# GatewayModbus.net
KiCad netlist of a schematic drawn in Altium Designer
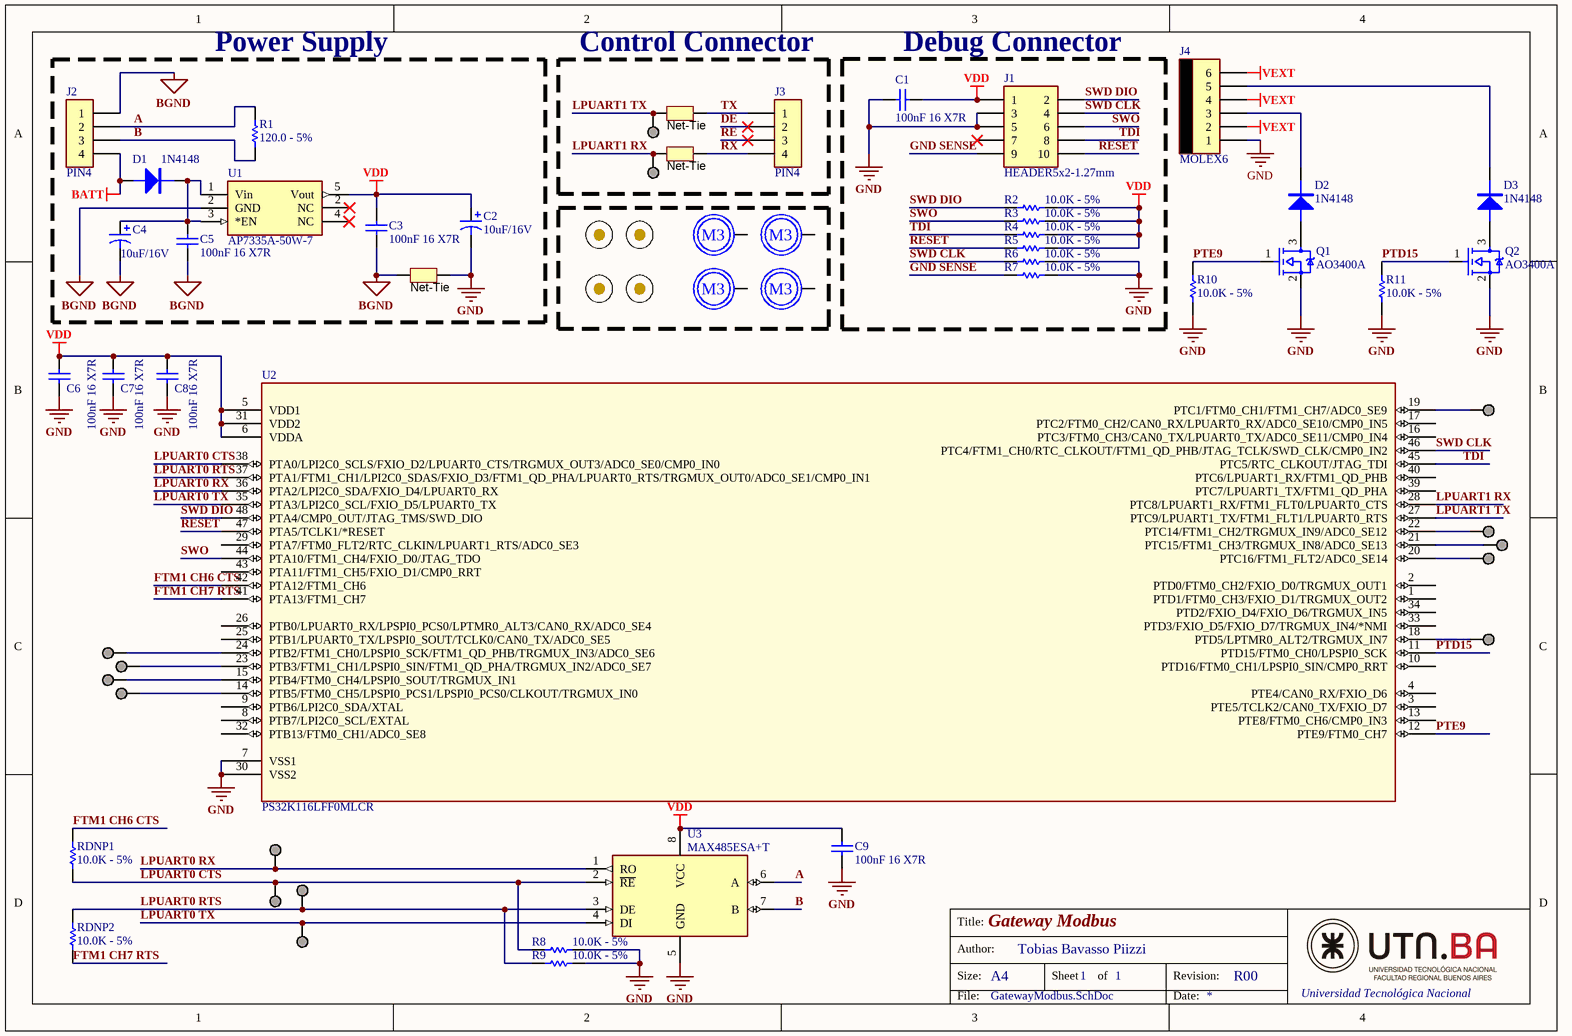
[diagram p0: GatewayModbus.SchDoc]

(export (version "E")
  (design (tool "Eeschema 10.0.6"))
  (components
    (comp (ref "C1")
      (value "100nF 16 X7R")
      (footprint "CAPC0603")
      (description "SMD Ceramic Chip Capacitor 0603")
      (libsource (lib "capacitors") (part "CAPC0603"))
    )
    (comp (ref "C2")
      (value "10uF/16V")
      (footprint "CAP POL TANT 1206")
      (description "Polarized Capacitor Tantalium")
      (libsource (lib "capacitors") (part "CAP POL TANT"))
    )
    (comp (ref "C3")
      (value "100nF 16 X7R")
      (footprint "CAPC0603")
      (description "SMD Ceramic Chip Capacitor 0603")
      (libsource (lib "capacitors") (part "CAPC0603"))
    )
    (comp (ref "C4")
      (value "10uF/16V")
      (footprint "CAP POL TANT 1206")
      (description "Polarized Capacitor Tantalium")
      (libsource (lib "capacitors") (part "CAP POL TANT"))
    )
    (comp (ref "C5")
      (value "100nF 16 X7R")
      (footprint "CAPC0603")
      (description "SMD Ceramic Chip Capacitor 0603")
      (libsource (lib "capacitors") (part "CAPC0603"))
    )
    (comp (ref "C6")
      (value "100nF 16 X7R")
      (footprint "CAPC0603")
      (description "SMD Ceramic Chip Capacitor 0603")
      (libsource (lib "capacitors") (part "CAPC0603"))
    )
    (comp (ref "C7")
      (value "100nF 16 X7R")
      (footprint "CAPC0603")
      (description "SMD Ceramic Chip Capacitor 0603")
      (libsource (lib "capacitors") (part "CAPC0603"))
    )
    (comp (ref "C8")
      (value "100nF 16 X7R")
      (footprint "CAPC0603")
      (description "SMD Ceramic Chip Capacitor 0603")
      (libsource (lib "capacitors") (part "CAPC0603"))
    )
    (comp (ref "C9")
      (value "100nF 16 X7R")
      (footprint "CAPC0603")
      (description "SMD Ceramic Chip Capacitor 0603")
      (libsource (lib "capacitors") (part "CAPC0603"))
    )
    (comp (ref "D1")
      (value "1N4148")
      (footprint "SOD323")
      (description "Small Signal Diode")
      (libsource (lib "diodes") (part "1N4148"))
    )
    (comp (ref "D2")
      (value "1N4148")
      (footprint "SOD323")
      (description "Small Signal Diode")
      (libsource (lib "diodes") (part "1N4148"))
    )
    (comp (ref "D3")
      (value "1N4148")
      (footprint "SOD323")
      (description "Small Signal Diode")
      (libsource (lib "diodes") (part "1N4148"))
    )
    (comp (ref "FID1")
      (value "Fiducial")
      (footprint "Fiducial10-20")
      (description "Fiducial mark.  There is nothing to buy or mount.. No entry in BOM.")
      (fields (field (name "SYMBOLCREATOR") "codlsc") (field (name "PUBLISHER") "Texas Instruments"))
      (libsource (lib "pcbStandard") (part "Fiducial"))
    )
    (comp (ref "FID2")
      (value "Fiducial")
      (footprint "Fiducial10-20")
      (description "Fiducial mark.  There is nothing to buy or mount.. No entry in BOM.")
      (fields (field (name "SYMBOLCREATOR") "codlsc") (field (name "PUBLISHER") "Texas Instruments"))
      (libsource (lib "pcbStandard") (part "Fiducial"))
    )
    (comp (ref "FID3")
      (value "Fiducial")
      (footprint "Fiducial10-20")
      (description "Fiducial mark.  There is nothing to buy or mount.. No entry in BOM.")
      (fields (field (name "SYMBOLCREATOR") "codlsc") (field (name "PUBLISHER") "Texas Instruments"))
      (libsource (lib "pcbStandard") (part "Fiducial"))
    )
    (comp (ref "FID4")
      (value "Fiducial")
      (footprint "Fiducial10-20")
      (description "Fiducial mark.  There is nothing to buy or mount.. No entry in BOM.")
      (fields (field (name "SYMBOLCREATOR") "codlsc") (field (name "PUBLISHER") "Texas Instruments"))
      (libsource (lib "pcbStandard") (part "Fiducial"))
    )
    (comp (ref "J1")
      (value "HEADER5x2-1.27mm")
      (footprint "PAD10-2X05-HH")
      (description "PAD10-2X05-HH")
      (libsource (lib "connectors") (part "HEADER5x2-1.27mm"))
    )
    (comp (ref "J2") (value "PIN4") (footprint "SIP4") (libsource (lib "connectors") (part "PIN4")))
    (comp (ref "J3") (value "PIN4") (footprint "SIP4") (libsource (lib "") (part "PIN4_1")))
    (comp (ref "J4") (value "MOLEX6") (footprint "MOLEX6") (libsource (lib "connectors") (part "MOLEX6")))
    (comp (ref "MH1")
      (value "M3 Mount Hole")
      (footprint "M3_MOUNTING_HOLE")
      (description "M3 Mounting Hole")
      (libsource (lib "pcbStandard") (part "M3 Mount Hole"))
    )
    (comp (ref "MH2")
      (value "M3 Mount Hole")
      (footprint "M3_MOUNTING_HOLE")
      (description "M3 Mounting Hole")
      (libsource (lib "pcbStandard") (part "M3 Mount Hole"))
    )
    (comp (ref "MH3")
      (value "M3 Mount Hole")
      (footprint "M3_MOUNTING_HOLE")
      (description "M3 Mounting Hole")
      (libsource (lib "pcbStandard") (part "M3 Mount Hole"))
    )
    (comp (ref "MH4")
      (value "M3 Mount Hole")
      (footprint "M3_MOUNTING_HOLE")
      (description "M3 Mounting Hole")
      (libsource (lib "pcbStandard") (part "M3 Mount Hole"))
    )
    (comp (ref "NT1")
      (value "Net-Tie")
      (footprint "Net-Tie_50milWide_30milLong")
      (description "Single point connection between nets.")
      (fields (field (name "SYMBOLCREATOR") "codlsc") (field (name "PUBLISHER") "Texas Instruments"))
      (libsource (lib "pcbStandard") (part "Net-Tie"))
    )
    (comp (ref "NT2")
      (value "Net-Tie")
      (footprint "Net-Tie_50milWide_30milLong")
      (description "Single point connection between nets.")
      (fields (field (name "SYMBOLCREATOR") "codlsc") (field (name "PUBLISHER") "Texas Instruments"))
      (libsource (lib "pcbStandard") (part "Net-Tie"))
    )
    (comp (ref "NT3")
      (value "Net-Tie")
      (footprint "Net-Tie_50milWide_30milLong")
      (description "Single point connection between nets.")
      (fields (field (name "SYMBOLCREATOR") "codlsc") (field (name "PUBLISHER") "Texas Instruments"))
      (libsource (lib "pcbStandard") (part "Net-Tie"))
    )
    (comp (ref "Q1")
      (value "AO3400A")
      (footprint "SOT-23")
      (description "30V 5.8A 35mΩ@10V,5.8A 1.4W 1.4V@250uA 1 N-Channel SOT-23 MOSFETs ROHS")
      (libsource (lib "nmos") (part "AO3400A"))
    )
    (comp (ref "Q2")
      (value "AO3400A")
      (footprint "SOT-23")
      (description "30V 5.8A 35mΩ@10V,5.8A 1.4W 1.4V@250uA 1 N-Channel SOT-23 MOSFETs ROHS")
      (libsource (lib "nmos") (part "AO3400A"))
    )
    (comp (ref "R1")
      (value "120.0 - 5%")
      (footprint "RESC0603")
      (description "SMD Chip Resistor 0603")
      (libsource (lib "resistors") (part "RESC 0603"))
    )
    (comp (ref "R2")
      (value "10.0K - 5%")
      (footprint "RESC0603")
      (description "SMD Chip Resistor 0603")
      (libsource (lib "resistors") (part "RESC 0603"))
    )
    (comp (ref "R3")
      (value "10.0K - 5%")
      (footprint "RESC0603")
      (description "SMD Chip Resistor 0603")
      (libsource (lib "resistors") (part "RESC 0603"))
    )
    (comp (ref "R4")
      (value "10.0K - 5%")
      (footprint "RESC0603")
      (description "SMD Chip Resistor 0603")
      (libsource (lib "resistors") (part "RESC 0603"))
    )
    (comp (ref "R5")
      (value "10.0K - 5%")
      (footprint "RESC0603")
      (description "SMD Chip Resistor 0603")
      (libsource (lib "resistors") (part "RESC 0603"))
    )
    (comp (ref "R6")
      (value "10.0K - 5%")
      (footprint "RESC0603")
      (description "SMD Chip Resistor 0603")
      (libsource (lib "resistors") (part "RESC 0603"))
    )
    (comp (ref "R7")
      (value "10.0K - 5%")
      (footprint "RESC0603")
      (description "SMD Chip Resistor 0603")
      (libsource (lib "resistors") (part "RESC 0603"))
    )
    (comp (ref "R8")
      (value "10.0K - 5%")
      (footprint "RESC0603")
      (description "SMD Chip Resistor 0603")
      (libsource (lib "resistors") (part "RESC 0603"))
    )
    (comp (ref "R9")
      (value "10.0K - 5%")
      (footprint "RESC0603")
      (description "SMD Chip Resistor 0603")
      (libsource (lib "resistors") (part "RESC 0603"))
    )
    (comp (ref "R10")
      (value "10.0K - 5%")
      (footprint "RESC0603")
      (description "SMD Chip Resistor 0603")
      (libsource (lib "resistors") (part "RESC 0603"))
    )
    (comp (ref "R11")
      (value "10.0K - 5%")
      (footprint "RESC0603")
      (description "SMD Chip Resistor 0603")
      (libsource (lib "resistors") (part "RESC 0603"))
    )
    (comp (ref "RDNP1")
      (value "10.0K - 5%")
      (footprint "RESC0603")
      (description "SMD Chip Resistor 0603")
      (libsource (lib "resistors") (part "RESC 0603"))
    )
    (comp (ref "RDNP2")
      (value "10.0K - 5%")
      (footprint "RESC0603")
      (description "SMD Chip Resistor 0603")
      (libsource (lib "resistors") (part "RESC 0603"))
    )
    (comp (ref "TP1")
      (value "~")
      (footprint "TP_SMD_Ø1.0mm")
      (description "TEST POINT.  No entry in BOM.")
      (fields (field (name "PUBLISHER") "Texas Instruments"))
      (libsource (lib "pcbStandard") (part "TESTPOINT"))
    )
    (comp (ref "TP2")
      (value "~")
      (footprint "TP_SMD_Ø1.0mm")
      (description "TEST POINT.  No entry in BOM.")
      (fields (field (name "PUBLISHER") "Texas Instruments"))
      (libsource (lib "pcbStandard") (part "TESTPOINT"))
    )
    (comp (ref "TP3")
      (value "~")
      (footprint "TP_SMD_Ø0.6mm")
      (description "TEST POINT.  No entry in BOM.")
      (fields (field (name "PUBLISHER") "Texas Instruments"))
      (libsource (lib "pcbStandard") (part "TESTPOINT"))
    )
    (comp (ref "TP4")
      (value "~")
      (footprint "TP_SMD_Ø0.6mm")
      (description "TEST POINT.  No entry in BOM.")
      (fields (field (name "PUBLISHER") "Texas Instruments"))
      (libsource (lib "pcbStandard") (part "TESTPOINT"))
    )
    (comp (ref "TP5")
      (value "~")
      (footprint "TP_SMD_Ø0.6mm")
      (description "TEST POINT.  No entry in BOM.")
      (fields (field (name "PUBLISHER") "Texas Instruments"))
      (libsource (lib "pcbStandard") (part "TESTPOINT"))
    )
    (comp (ref "TP6")
      (value "~")
      (footprint "TP_SMD_Ø0.6mm")
      (description "TEST POINT.  No entry in BOM.")
      (fields (field (name "PUBLISHER") "Texas Instruments"))
      (libsource (lib "pcbStandard") (part "TESTPOINT"))
    )
    (comp (ref "TP7")
      (value "~")
      (footprint "TP_SMD_Ø0.6mm")
      (description "TEST POINT.  No entry in BOM.")
      (fields (field (name "PUBLISHER") "Texas Instruments"))
      (libsource (lib "pcbStandard") (part "TESTPOINT"))
    )
    (comp (ref "TP8")
      (value "~")
      (footprint "TP_SMD_Ø0.6mm")
      (description "TEST POINT.  No entry in BOM.")
      (fields (field (name "PUBLISHER") "Texas Instruments"))
      (libsource (lib "pcbStandard") (part "TESTPOINT"))
    )
    (comp (ref "TP9")
      (value "~")
      (footprint "TP_SMD_Ø0.6mm")
      (description "TEST POINT.  No entry in BOM.")
      (fields (field (name "PUBLISHER") "Texas Instruments"))
      (libsource (lib "pcbStandard") (part "TESTPOINT"))
    )
    (comp (ref "TP10")
      (value "~")
      (footprint "TP_SMD_Ø0.6mm")
      (description "TEST POINT.  No entry in BOM.")
      (fields (field (name "PUBLISHER") "Texas Instruments"))
      (libsource (lib "pcbStandard") (part "TESTPOINT"))
    )
    (comp (ref "TP11")
      (value "~")
      (footprint "TP_SMD_Ø0.6mm")
      (description "TEST POINT.  No entry in BOM.")
      (fields (field (name "PUBLISHER") "Texas Instruments"))
      (libsource (lib "pcbStandard") (part "TESTPOINT"))
    )
    (comp (ref "TP12")
      (value "~")
      (footprint "TP_SMD_Ø1.0mm")
      (description "TEST POINT.  No entry in BOM.")
      (fields (field (name "PUBLISHER") "Texas Instruments"))
      (libsource (lib "pcbStandard") (part "TESTPOINT"))
    )
    (comp (ref "TP13")
      (value "~")
      (footprint "TP_SMD_Ø1.0mm")
      (description "TEST POINT.  No entry in BOM.")
      (fields (field (name "PUBLISHER") "Texas Instruments"))
      (libsource (lib "pcbStandard") (part "TESTPOINT"))
    )
    (comp (ref "TP14")
      (value "~")
      (footprint "TP_SMD_Ø1.0mm")
      (description "TEST POINT.  No entry in BOM.")
      (fields (field (name "PUBLISHER") "Texas Instruments"))
      (libsource (lib "pcbStandard") (part "TESTPOINT"))
    )
    (comp (ref "TP15")
      (value "~")
      (footprint "TP_SMD_Ø1.0mm")
      (description "TEST POINT.  No entry in BOM.")
      (fields (field (name "PUBLISHER") "Texas Instruments"))
      (libsource (lib "pcbStandard") (part "TESTPOINT"))
    )
    (comp (ref "U1")
      (value "AP7335A-50W-7")
      (footprint "SOT-23-5")
      (description "IC REG LINEAR 5V 300MA SOT25")
      (libsource (lib "regulators") (part "AP7335A-50W-7"))
    )
    (comp (ref "U2")
      (value "PS32K116LFF0MLCR")
      (footprint "LQFP48-NXP")
      (description "Microcontroladores ARM - MCU S32K116, M0+, Flash 128K, RAM 17KB")
      (fields
        (field (name "MANUFACTURER_PART_NUMBER") "ps32k116lff0mlcr")
        (field (name "COPYRIGHT") "Copyright (C) 2016 Accelerated Designs. All rights reserved")
      )
      (libsource (lib "nxp") (part "PS32K116LFF0MLCR"))
    )
    (comp (ref "U3")
      (value "MAX485ESA+T")
      (footprint "SOIC8")
      (description "1/1 Transceiver Half RS422, RS485 8-SOIC")
      (fields (field (name "MP") "MAX485ESA") (field (name "MF") "Maxim Integrated"))
      (libsource (lib "integrated_circuits") (part "MAX485ESA+T"))
    )
  )
  (nets
    (net (code "1") (name "/A") (class "Default")
      (node (ref "J2") (pin "2") (pinfunction "2_2") (pintype "passive"))
      (node (ref "R1") (pin "1") (pinfunction "1_1") (pintype "passive"))
      (node (ref "U3") (pin "6") (pinfunction "A_6") (pintype "bidirectional"))
    )
    (net (code "2") (name "/B") (class "Default")
      (node (ref "J2") (pin "3") (pinfunction "3_3") (pintype "passive"))
      (node (ref "R1") (pin "2") (pinfunction "2_2") (pintype "passive"))
      (node (ref "U3") (pin "7") (pinfunction "B_7") (pintype "bidirectional"))
    )
    (net (code "3") (name "/DE") (class "Default")
      (node (ref "J3") (pin "2") (pinfunction "2_2") (pintype "passive+no_connect"))
    )
    (net (code "4") (name "/FTM1 CH6 CTS") (class "Default")
      (node (ref "RDNP1") (pin "1") (pinfunction "1_1") (pintype "passive"))
      (node (ref "U2") (pin "42") (pinfunction "PTA12/FTM1_CH6_42") (pintype "bidirectional"))
    )
    (net (code "5") (name "/FTM1 CH7 RTS") (class "Default")
      (node (ref "RDNP2") (pin "2") (pinfunction "2_2") (pintype "passive"))
      (node (ref "U2") (pin "41") (pinfunction "PTA13/FTM1_CH7_41") (pintype "bidirectional"))
    )
    (net (code "6") (name "/GND SENSE") (class "Default")
      (node (ref "J1") (pin "9") (pinfunction "9_9") (pintype "passive"))
      (node (ref "R7") (pin "2") (pinfunction "2_2") (pintype "passive"))
    )
    (net (code "7") (name "/LPUART0 CTS") (class "Default")
      (node (ref "R8") (pin "2") (pinfunction "2_2") (pintype "passive"))
      (node (ref "RDNP1") (pin "2") (pinfunction "2_2") (pintype "passive"))
      (node (ref "TP14") (pin "1") (pintype "passive"))
      (node (ref "U2") (pin "38") (pinfunction "PTA0/LPI2C0_SCLS/FXIO_D2/LPUART0_CTS/TRGMUX_OUT3/ADC0_SE0/CMP0_IN0_38") (pintype "bidirectional"))
      (node (ref "U3") (pin "2") (pinfunction "~{RE}_2") (pintype "input"))
    )
    (net (code "8") (name "/LPUART0 RTS") (class "Default")
      (node (ref "R9") (pin "2") (pinfunction "2_2") (pintype "passive"))
      (node (ref "RDNP2") (pin "1") (pinfunction "1_1") (pintype "passive"))
      (node (ref "TP13") (pin "1") (pintype "passive"))
      (node (ref "U2") (pin "37") (pinfunction "PTA1/FTM1_CH1/LPI2C0_SDAS/FXIO_D3/FTM1_QD_PHA/LPUART0_RTS/TRGMUX_OUT0/ADC0_SE1/CMP0_IN1_37") (pintype "bidirectional"))
      (node (ref "U3") (pin "3") (pinfunction "DE_3") (pintype "input"))
    )
    (net (code "9") (name "/LPUART0 RX") (class "Default")
      (node (ref "TP12") (pin "1") (pintype "passive"))
      (node (ref "U2") (pin "36") (pinfunction "PTA2/LPI2C0_SDA/FXIO_D4/LPUART0_RX_36") (pintype "bidirectional"))
      (node (ref "U3") (pin "1") (pinfunction "RO_1") (pintype "output"))
    )
    (net (code "10") (name "/LPUART0 TX") (class "Default")
      (node (ref "TP15") (pin "1") (pintype "passive"))
      (node (ref "U2") (pin "35") (pinfunction "PTA3/LPI2C0_SCL/FXIO_D5/LPUART0_TX_35") (pintype "bidirectional"))
      (node (ref "U3") (pin "4") (pinfunction "DI_4") (pintype "input"))
    )
    (net (code "11") (name "/LPUART1 RX") (class "Default")
      (node (ref "NT2") (pin "1") (pinfunction "1_1") (pintype "passive"))
      (node (ref "TP2") (pin "1") (pintype "passive"))
      (node (ref "U2") (pin "28") (pinfunction "PTC8/LPUART1_RX/FTM1_FLT0/LPUART0_CTS_28") (pintype "bidirectional"))
    )
    (net (code "12") (name "/LPUART1 TX") (class "Default")
      (node (ref "NT1") (pin "1") (pinfunction "1_1") (pintype "passive"))
      (node (ref "TP1") (pin "1") (pintype "passive"))
      (node (ref "U2") (pin "27") (pinfunction "PTC9/LPUART1_TX/FTM1_FLT1/LPUART0_RTS_27") (pintype "bidirectional"))
    )
    (net (code "13") (name "/PTD15") (class "Default")
      (node (ref "Q2") (pin "1") (pinfunction "G_1") (pintype "passive"))
      (node (ref "R11") (pin "1") (pinfunction "1_1") (pintype "passive"))
      (node (ref "U2") (pin "11") (pinfunction "PTD15/FTM0_CH0/LPSPI0_SCK_11") (pintype "bidirectional"))
    )
    (net (code "14") (name "/PTE9") (class "Default")
      (node (ref "Q1") (pin "1") (pinfunction "G_1") (pintype "passive"))
      (node (ref "R10") (pin "1") (pinfunction "1_1") (pintype "passive"))
      (node (ref "U2") (pin "12") (pinfunction "PTE9/FTM0_CH7_12") (pintype "bidirectional"))
    )
    (net (code "15") (name "/RE") (class "Default")
      (node (ref "J3") (pin "3") (pinfunction "3_3") (pintype "passive+no_connect"))
    )
    (net (code "16") (name "/RX") (class "Default")
      (node (ref "J3") (pin "4") (pinfunction "4_4") (pintype "passive"))
      (node (ref "NT2") (pin "2") (pinfunction "2_2") (pintype "passive"))
    )
    (net (code "17") (name "/SWD CLK") (class "Default")
      (node (ref "J1") (pin "4") (pinfunction "4_4") (pintype "passive"))
      (node (ref "R6") (pin "2") (pinfunction "2_2") (pintype "passive"))
      (node (ref "U2") (pin "46") (pinfunction "PTC4/FTM1_CH0/RTC_CLKOUT/FTM1_QD_PHB/JTAG_TCLK/SWD_CLK/CMP0_IN2_46") (pintype "bidirectional"))
    )
    (net (code "18") (name "/SWD DIO") (class "Default")
      (node (ref "J1") (pin "2") (pinfunction "2_2") (pintype "passive"))
      (node (ref "R2") (pin "2") (pinfunction "2_2") (pintype "passive"))
      (node (ref "U2") (pin "48") (pinfunction "PTA4/CMP0_OUT/JTAG_TMS/SWD_DIO_48") (pintype "bidirectional"))
    )
    (net (code "19") (name "/SWO") (class "Default")
      (node (ref "J1") (pin "6") (pinfunction "6_6") (pintype "passive"))
      (node (ref "R3") (pin "2") (pinfunction "2_2") (pintype "passive"))
      (node (ref "U2") (pin "44") (pinfunction "PTA10/FTM1_CH4/FXIO_D0/JTAG_TDO_44") (pintype "bidirectional"))
    )
    (net (code "20") (name "/TDI") (class "Default")
      (node (ref "J1") (pin "8") (pinfunction "8_8") (pintype "passive"))
      (node (ref "R4") (pin "2") (pinfunction "2_2") (pintype "passive"))
      (node (ref "U2") (pin "45") (pinfunction "PTC5/RTC_CLKOUT/JTAG_TDI_45") (pintype "bidirectional"))
    )
    (net (code "21") (name "/TX") (class "Default")
      (node (ref "J3") (pin "1") (pinfunction "1_1") (pintype "passive"))
      (node (ref "NT1") (pin "2") (pinfunction "2_2") (pintype "passive"))
    )
    (net (code "22") (name "/~{RESET}") (class "Default")
      (node (ref "J1") (pin "10") (pinfunction "10_10") (pintype "passive"))
      (node (ref "R5") (pin "2") (pinfunction "2_2") (pintype "passive"))
      (node (ref "U2") (pin "47") (pinfunction "PTA5/TCLK1/*RESET_47") (pintype "bidirectional"))
    )
    (net (code "23") (name "BATT") (class "Default")
      (node (ref "D1") (pin "A") (pintype "passive"))
      (node (ref "J2") (pin "4") (pinfunction "4_4") (pintype "passive"))
    )
    (net (code "24") (name "BGND") (class "Default")
      (node (ref "C3") (pin "1") (pinfunction "1_1") (pintype "passive"))
      (node (ref "C4") (pin "2") (pinfunction "2_2") (pintype "passive"))
      (node (ref "C5") (pin "1") (pinfunction "1_1") (pintype "passive"))
      (node (ref "J2") (pin "1") (pinfunction "1_1") (pintype "passive"))
      (node (ref "NT3") (pin "1") (pinfunction "1_1") (pintype "passive"))
      (node (ref "U1") (pin "2") (pinfunction "GND_2") (pintype "power_in"))
    )
    (net (code "25") (name "GND") (class "Default")
      (node (ref "C1") (pin "1") (pinfunction "1_1") (pintype "passive"))
      (node (ref "C2") (pin "2") (pinfunction "2_2") (pintype "passive"))
      (node (ref "C6") (pin "1") (pinfunction "1_1") (pintype "passive"))
      (node (ref "C7") (pin "1") (pinfunction "1_1") (pintype "passive"))
      (node (ref "C8") (pin "1") (pinfunction "1_1") (pintype "passive"))
      (node (ref "C9") (pin "2") (pinfunction "2_2") (pintype "passive"))
      (node (ref "J1") (pin "3") (pinfunction "3_3") (pintype "passive"))
      (node (ref "J1") (pin "5") (pinfunction "5_5") (pintype "passive"))
      (node (ref "J4") (pin "1") (pinfunction "1_1") (pintype "passive"))
      (node (ref "NT3") (pin "2") (pinfunction "2_2") (pintype "passive"))
      (node (ref "Q1") (pin "2") (pinfunction "S_2") (pintype "passive"))
      (node (ref "Q2") (pin "2") (pinfunction "S_2") (pintype "passive"))
      (node (ref "R10") (pin "2") (pinfunction "2_2") (pintype "passive"))
      (node (ref "R11") (pin "2") (pinfunction "2_2") (pintype "passive"))
      (node (ref "R6") (pin "1") (pinfunction "1_1") (pintype "passive"))
      (node (ref "R7") (pin "1") (pinfunction "1_1") (pintype "passive"))
      (node (ref "R8") (pin "1") (pinfunction "1_1") (pintype "passive"))
      (node (ref "R9") (pin "1") (pinfunction "1_1") (pintype "passive"))
      (node (ref "U2") (pin "30") (pinfunction "VSS2_30") (pintype "power_in"))
      (node (ref "U2") (pin "7") (pinfunction "VSS1_7") (pintype "power_in"))
      (node (ref "U3") (pin "5") (pinfunction "GND_5") (pintype "power_in"))
    )
    (net (code "26") (name "Net-(D2-PadK)") (class "Default")
      (node (ref "D2") (pin "K") (pintype "passive"))
      (node (ref "J4") (pin "3") (pinfunction "3_3") (pintype "passive"))
    )
    (net (code "27") (name "Net-(D3-PadK)") (class "Default")
      (node (ref "D3") (pin "K") (pintype "passive"))
      (node (ref "J4") (pin "5") (pinfunction "5_5") (pintype "passive"))
    )
    (net (code "28") (name "Net-(Q1-D)") (class "Default")
      (node (ref "D2") (pin "A") (pintype "passive"))
      (node (ref "Q1") (pin "3") (pinfunction "D_3") (pintype "passive"))
    )
    (net (code "29") (name "Net-(Q2-D)") (class "Default")
      (node (ref "D3") (pin "A") (pintype "passive"))
      (node (ref "Q2") (pin "3") (pinfunction "D_3") (pintype "passive"))
    )
    (net (code "30") (name "Net-(U1-*EN)") (class "Default")
      (node (ref "C4") (pin "1") (pinfunction "1_1") (pintype "passive"))
      (node (ref "C5") (pin "2") (pinfunction "2_2") (pintype "passive"))
      (node (ref "D1") (pin "K") (pintype "passive"))
      (node (ref "U1") (pin "1") (pinfunction "Vin_1") (pintype "power_in"))
      (node (ref "U1") (pin "3") (pinfunction "*EN_3") (pintype "input"))
    )
    (net (code "31") (name "Net-(U2-PTB2{slash}FTM1_CH0{slash}LPSPI0_SCK{slash}FTM1_QD_PHB{slash}TRGMUX_IN3{slash}ADC0_SE6)") (class "Default")
      (node (ref "TP5") (pin "1") (pintype "passive"))
      (node (ref "U2") (pin "24") (pinfunction "PTB2/FTM1_CH0/LPSPI0_SCK/FTM1_QD_PHB/TRGMUX_IN3/ADC0_SE6_24") (pintype "bidirectional"))
    )
    (net (code "32") (name "Net-(U2-PTB3{slash}FTM1_CH1{slash}LPSPI0_SIN{slash}FTM1_QD_PHA{slash}TRGMUX_IN2{slash}ADC0_SE7)") (class "Default")
      (node (ref "TP6") (pin "1") (pintype "passive"))
      (node (ref "U2") (pin "23") (pinfunction "PTB3/FTM1_CH1/LPSPI0_SIN/FTM1_QD_PHA/TRGMUX_IN2/ADC0_SE7_23") (pintype "bidirectional"))
    )
    (net (code "33") (name "Net-(U2-PTB4{slash}FTM0_CH4{slash}LPSPI0_SOUT{slash}TRGMUX_IN1)") (class "Default")
      (node (ref "TP7") (pin "1") (pintype "passive"))
      (node (ref "U2") (pin "15") (pinfunction "PTB4/FTM0_CH4/LPSPI0_SOUT/TRGMUX_IN1_15") (pintype "bidirectional"))
    )
    (net (code "34") (name "Net-(U2-PTB5{slash}FTM0_CH5{slash}LPSPI0_PCS1{slash}LPSPI0_PCS0{slash}CLKOUT{slash}TRGMUX_IN0)") (class "Default")
      (node (ref "TP8") (pin "1") (pintype "passive"))
      (node (ref "U2") (pin "14") (pinfunction "PTB5/FTM0_CH5/LPSPI0_PCS1/LPSPI0_PCS0/CLKOUT/TRGMUX_IN0_14") (pintype "bidirectional"))
    )
    (net (code "35") (name "Net-(U2-PTC1{slash}FTM0_CH1{slash}FTM1_CH7{slash}ADC0_SE9)") (class "Default")
      (node (ref "TP9") (pin "1") (pintype "passive"))
      (node (ref "U2") (pin "19") (pinfunction "PTC1/FTM0_CH1/FTM1_CH7/ADC0_SE9_19") (pintype "bidirectional"))
    )
    (net (code "36") (name "Net-(U2-PTC14{slash}FTM1_CH2{slash}TRGMUX_IN9{slash}ADC0_SE12)") (class "Default")
      (node (ref "TP3") (pin "1") (pintype "passive"))
      (node (ref "U2") (pin "22") (pinfunction "PTC14/FTM1_CH2/TRGMUX_IN9/ADC0_SE12_22") (pintype "bidirectional"))
    )
    (net (code "37") (name "Net-(U2-PTC15{slash}FTM1_CH3{slash}TRGMUX_IN8{slash}ADC0_SE13)") (class "Default")
      (node (ref "TP4") (pin "1") (pintype "passive"))
      (node (ref "U2") (pin "21") (pinfunction "PTC15/FTM1_CH3/TRGMUX_IN8/ADC0_SE13_21") (pintype "bidirectional"))
    )
    (net (code "38") (name "Net-(U2-PTC16{slash}FTM1_FLT2{slash}ADC0_SE14)") (class "Default")
      (node (ref "TP11") (pin "1") (pintype "passive"))
      (node (ref "U2") (pin "20") (pinfunction "PTC16/FTM1_FLT2/ADC0_SE14_20") (pintype "bidirectional"))
    )
    (net (code "39") (name "Net-(U2-PTD5{slash}LPTMR0_ALT2{slash}TRGMUX_IN7)") (class "Default")
      (node (ref "TP10") (pin "1") (pintype "passive"))
      (node (ref "U2") (pin "18") (pinfunction "PTD5/LPTMR0_ALT2/TRGMUX_IN7_18") (pintype "bidirectional"))
    )
    (net (code "40") (name "VDD") (class "Default")
      (node (ref "C1") (pin "2") (pinfunction "2_2") (pintype "passive"))
      (node (ref "C2") (pin "1") (pinfunction "1_1") (pintype "passive"))
      (node (ref "C3") (pin "2") (pinfunction "2_2") (pintype "passive"))
      (node (ref "C6") (pin "2") (pinfunction "2_2") (pintype "passive"))
      (node (ref "C7") (pin "2") (pinfunction "2_2") (pintype "passive"))
      (node (ref "C8") (pin "2") (pinfunction "2_2") (pintype "passive"))
      (node (ref "C9") (pin "1") (pinfunction "1_1") (pintype "passive"))
      (node (ref "J1") (pin "1") (pinfunction "1_1") (pintype "passive"))
      (node (ref "R2") (pin "1") (pinfunction "1_1") (pintype "passive"))
      (node (ref "R3") (pin "1") (pinfunction "1_1") (pintype "passive"))
      (node (ref "R4") (pin "1") (pinfunction "1_1") (pintype "passive"))
      (node (ref "R5") (pin "1") (pinfunction "1_1") (pintype "passive"))
      (node (ref "U1") (pin "5") (pinfunction "Vout_5") (pintype "output"))
      (node (ref "U2") (pin "31") (pinfunction "VDD2_31") (pintype "power_in"))
      (node (ref "U2") (pin "5") (pinfunction "VDD1_5") (pintype "power_in"))
      (node (ref "U2") (pin "6") (pinfunction "VDDA_6") (pintype "power_in"))
      (node (ref "U3") (pin "8") (pinfunction "VCC_8") (pintype "power_in"))
    )
    (net (code "41") (name "VEXT") (class "Default")
      (node (ref "J4") (pin "2") (pinfunction "2_2") (pintype "passive"))
      (node (ref "J4") (pin "4") (pinfunction "4_4") (pintype "passive"))
      (node (ref "J4") (pin "6") (pinfunction "6_6") (pintype "passive"))
    )
    (net (code "42") (name "unconnected-(J1-Pad7)") (class "Default")
      (node (ref "J1") (pin "7") (pinfunction "7_7") (pintype "passive+no_connect"))
    )
    (net (code "43") (name "unconnected-(MH1-TP-Pad1)") (class "Default")
      (node (ref "MH1") (pin "1") (pinfunction "TP_1") (pintype "passive"))
    )
    (net (code "44") (name "unconnected-(MH2-TP-Pad1)") (class "Default")
      (node (ref "MH2") (pin "1") (pinfunction "TP_1") (pintype "passive"))
    )
    (net (code "45") (name "unconnected-(MH3-TP-Pad1)") (class "Default")
      (node (ref "MH3") (pin "1") (pinfunction "TP_1") (pintype "passive"))
    )
    (net (code "46") (name "unconnected-(MH4-TP-Pad1)") (class "Default")
      (node (ref "MH4") (pin "1") (pinfunction "TP_1") (pintype "passive"))
    )
    (net (code "47") (name "unconnected-(U1-NC-Pad2)") (class "Default")
      (node (ref "U1") (pin "2") (pinfunction "NC_2") (pintype "power_in+no_connect"))
    )
    (net (code "48") (name "unconnected-(U1-NC-Pad4)") (class "Default")
      (node (ref "U1") (pin "4") (pinfunction "NC_4") (pintype "power_in+no_connect"))
    )
    (net (code "49") (name "unconnected-(U2-PTA7{slash}FTM0_FLT2{slash}RTC_CLKIN{slash}LPUART1_RTS{slash}ADC0_SE3-Pad29)") (class "Default")
      (node (ref "U2") (pin "29") (pinfunction "PTA7/FTM0_FLT2/RTC_CLKIN/LPUART1_RTS/ADC0_SE3_29") (pintype "bidirectional"))
    )
    (net (code "50") (name "unconnected-(U2-PTA11{slash}FTM1_CH5{slash}FXIO_D1{slash}CMP0_RRT-Pad43)") (class "Default")
      (node (ref "U2") (pin "43") (pinfunction "PTA11/FTM1_CH5/FXIO_D1/CMP0_RRT_43") (pintype "bidirectional"))
    )
    (net (code "51") (name "unconnected-(U2-PTB0{slash}LPUART0_RX{slash}LPSPI0_PCS0{slash}LPTMR0_ALT3{slash}CAN0_RX{slash}ADC0_SE4-Pad26)") (class "Default")
      (node (ref "U2") (pin "26") (pinfunction "PTB0/LPUART0_RX/LPSPI0_PCS0/LPTMR0_ALT3/CAN0_RX/ADC0_SE4_26") (pintype "bidirectional"))
    )
    (net (code "52") (name "unconnected-(U2-PTB1{slash}LPUART0_TX{slash}LPSPI0_SOUT{slash}TCLK0{slash}CAN0_TX{slash}ADC0_SE5-Pad25)") (class "Default")
      (node (ref "U2") (pin "25") (pinfunction "PTB1/LPUART0_TX/LPSPI0_SOUT/TCLK0/CAN0_TX/ADC0_SE5_25") (pintype "bidirectional"))
    )
    (net (code "53") (name "unconnected-(U2-PTB6{slash}LPI2C0_SDA{slash}XTAL-Pad9)") (class "Default")
      (node (ref "U2") (pin "9") (pinfunction "PTB6/LPI2C0_SDA/XTAL_9") (pintype "bidirectional"))
    )
    (net (code "54") (name "unconnected-(U2-PTB7{slash}LPI2C0_SCL{slash}EXTAL-Pad8)") (class "Default")
      (node (ref "U2") (pin "8") (pinfunction "PTB7/LPI2C0_SCL/EXTAL_8") (pintype "bidirectional"))
    )
    (net (code "55") (name "unconnected-(U2-PTB13{slash}FTM0_CH1{slash}ADC0_SE8-Pad32)") (class "Default")
      (node (ref "U2") (pin "32") (pinfunction "PTB13/FTM0_CH1/ADC0_SE8_32") (pintype "bidirectional"))
    )
    (net (code "56") (name "unconnected-(U2-PTC2{slash}FTM0_CH2{slash}CAN0_RX{slash}LPUART0_RX{slash}ADC0_SE10{slash}CMP0_IN5-Pad17)") (class "Default")
      (node (ref "U2") (pin "17") (pinfunction "PTC2/FTM0_CH2/CAN0_RX/LPUART0_RX/ADC0_SE10/CMP0_IN5_17") (pintype "bidirectional"))
    )
    (net (code "57") (name "unconnected-(U2-PTC3{slash}FTM0_CH3{slash}CAN0_TX{slash}LPUART0_TX{slash}ADC0_SE11{slash}CMP0_IN4-Pad16)") (class "Default")
      (node (ref "U2") (pin "16") (pinfunction "PTC3/FTM0_CH3/CAN0_TX/LPUART0_TX/ADC0_SE11/CMP0_IN4_16") (pintype "bidirectional"))
    )
    (net (code "58") (name "unconnected-(U2-PTC6{slash}LPUART1_RX{slash}FTM1_QD_PHB-Pad40)") (class "Default")
      (node (ref "U2") (pin "40") (pinfunction "PTC6/LPUART1_RX/FTM1_QD_PHB_40") (pintype "bidirectional"))
    )
    (net (code "59") (name "unconnected-(U2-PTC7{slash}LPUART1_TX{slash}FTM1_QD_PHA-Pad39)") (class "Default")
      (node (ref "U2") (pin "39") (pinfunction "PTC7/LPUART1_TX/FTM1_QD_PHA_39") (pintype "bidirectional"))
    )
    (net (code "60") (name "unconnected-(U2-PTD0{slash}FTM0_CH2{slash}FXIO_D0{slash}TRGMUX_OUT1-Pad2)") (class "Default")
      (node (ref "U2") (pin "2") (pinfunction "PTD0/FTM0_CH2/FXIO_D0/TRGMUX_OUT1_2") (pintype "bidirectional"))
    )
    (net (code "61") (name "unconnected-(U2-PTD1{slash}FTM0_CH3{slash}FXIO_D1{slash}TRGMUX_OUT2-Pad1)") (class "Default")
      (node (ref "U2") (pin "1") (pinfunction "PTD1/FTM0_CH3/FXIO_D1/TRGMUX_OUT2_1") (pintype "bidirectional"))
    )
    (net (code "62") (name "unconnected-(U2-PTD2{slash}FXIO_D4{slash}FXIO_D6{slash}TRGMUX_IN5-Pad34)") (class "Default")
      (node (ref "U2") (pin "34") (pinfunction "PTD2/FXIO_D4/FXIO_D6/TRGMUX_IN5_34") (pintype "bidirectional"))
    )
    (net (code "63") (name "unconnected-(U2-PTD3{slash}FXIO_D5{slash}FXIO_D7{slash}TRGMUX_IN4{slash}*NMI-Pad33)") (class "Default")
      (node (ref "U2") (pin "33") (pinfunction "PTD3/FXIO_D5/FXIO_D7/TRGMUX_IN4/*NMI_33") (pintype "bidirectional"))
    )
    (net (code "64") (name "unconnected-(U2-PTD16{slash}FTM0_CH1{slash}LPSPI0_SIN{slash}CMP0_RRT-Pad10)") (class "Default")
      (node (ref "U2") (pin "10") (pinfunction "PTD16/FTM0_CH1/LPSPI0_SIN/CMP0_RRT_10") (pintype "bidirectional"))
    )
    (net (code "65") (name "unconnected-(U2-PTE4{slash}CAN0_RX{slash}FXIO_D6-Pad4)") (class "Default")
      (node (ref "U2") (pin "4") (pinfunction "PTE4/CAN0_RX/FXIO_D6_4") (pintype "bidirectional"))
    )
    (net (code "66") (name "unconnected-(U2-PTE5{slash}TCLK2{slash}CAN0_TX{slash}FXIO_D7-Pad3)") (class "Default")
      (node (ref "U2") (pin "3") (pinfunction "PTE5/TCLK2/CAN0_TX/FXIO_D7_3") (pintype "bidirectional"))
    )
    (net (code "67") (name "unconnected-(U2-PTE8{slash}FTM0_CH6{slash}CMP0_IN3-Pad13)") (class "Default")
      (node (ref "U2") (pin "13") (pinfunction "PTE8/FTM0_CH6/CMP0_IN3_13") (pintype "bidirectional"))
    )
  )
)
